# Main.net
KiCad netlist of a schematic drawn in Altium Designer
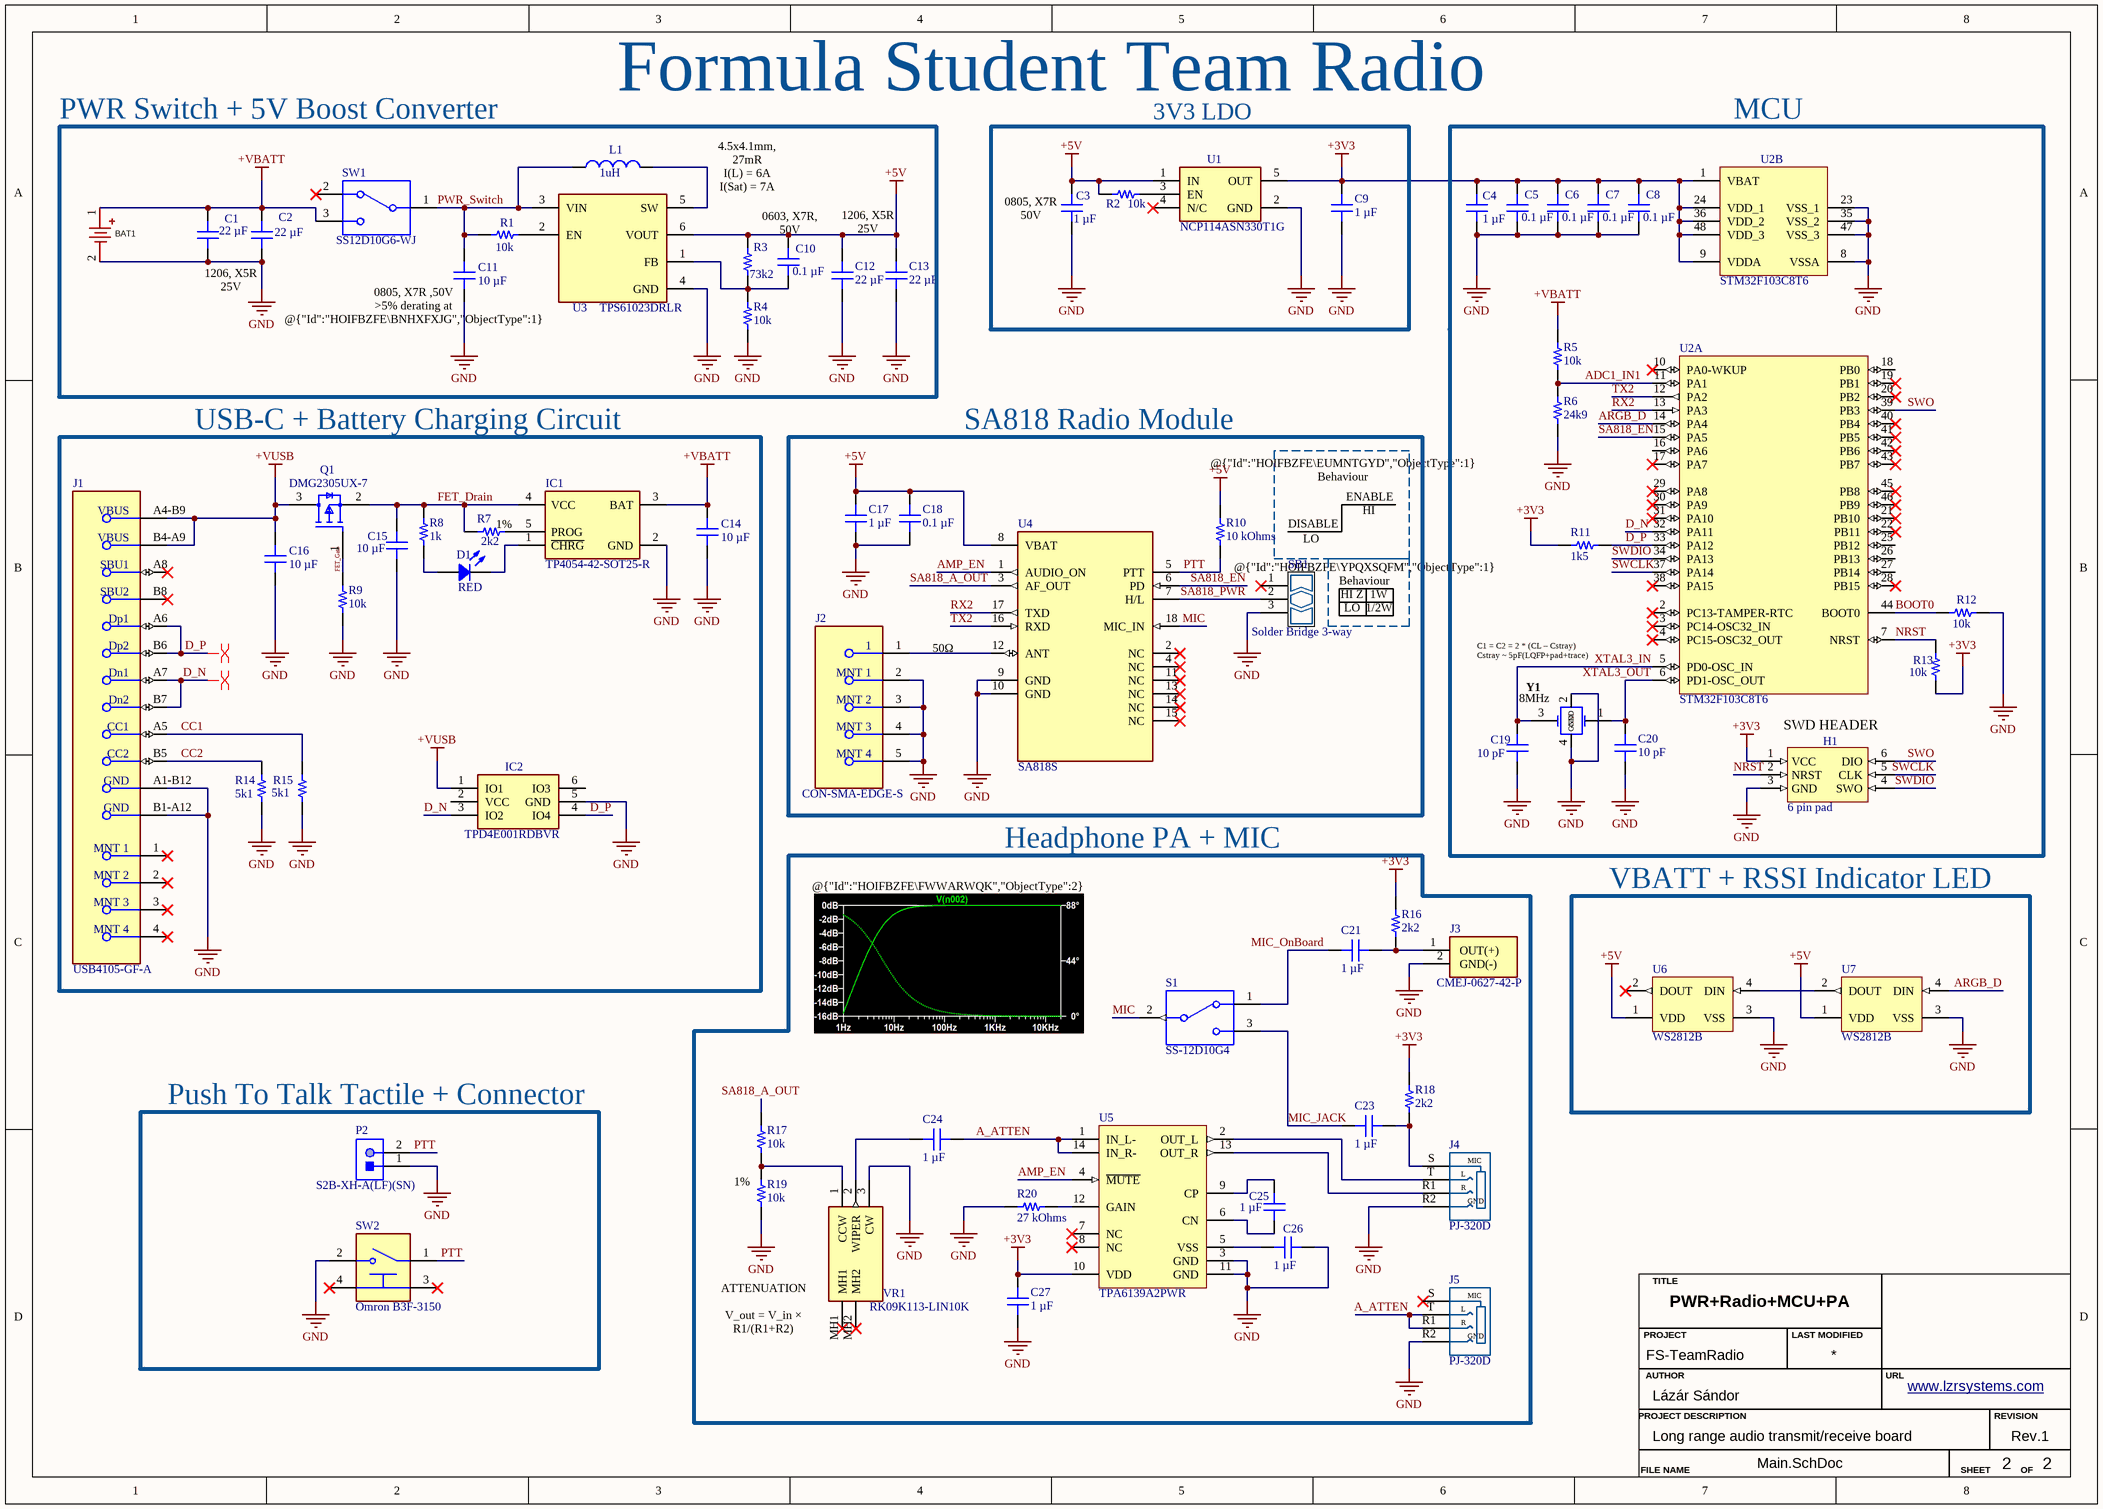
[diagram p0: Main.SchDoc]

(export (version "E")
  (design (tool "Eeschema 10.0.6"))
  (components
    (comp (ref "BAT1")
      (value "BH-123A-A1CJ002")
      (footprint "BAT-TH_BH-123A-A5BJ002")
      (fields (field (name "MANUFACTURER") "MYOUNG(美阳)"))
      (libsource (lib "Sandor Lazar") (part "BH-123A-A1CJ002"))
    )
    (comp (ref "C1")
      (value "22 µF")
      (footprint "MURATA CAP GRM31C 1206_3216")
      (description "CAP CER 22UF 25V X6S 1206")
      (fields
        (field (name "PART NUMBER") "GRM31CC81E226KE11L")
        (field (name "CAPACITANCE") "22 µF")
        (field (name "MANUFACTURER") "Murata Electronics")
      )
      (libsource (lib "Celestial Altium Library - altium_library") (part "Capacitor"))
    )
    (comp (ref "C2")
      (value "22 µF")
      (footprint "MURATA CAP GRM31C 1206_3216")
      (description "CAP CER 22UF 25V X6S 1206")
      (fields
        (field (name "PART NUMBER") "GRM31CC81E226KE11L")
        (field (name "CAPACITANCE") "22 µF")
        (field (name "MANUFACTURER") "Murata Electronics")
      )
      (libsource (lib "Celestial Altium Library - altium_library") (part "Capacitor"))
    )
    (comp (ref "C3")
      (value "1 µF")
      (footprint "MURATA GRT21 0805_2012")
      (description "CAP CER 1UF 50V X7R 0805")
      (fields
        (field (name "PART NUMBER") "GRT21BR71H105KE01L")
        (field (name "CAPACITANCE") "1 µF")
        (field (name "MANUFACTURER") "Murata Electronics")
      )
      (libsource (lib "Celestial Altium Library - altium_library") (part "Capacitor"))
    )
    (comp (ref "C4")
      (value "1 µF")
      (footprint "MURATA GRT21 0805_2012")
      (description "CAP CER 1UF 50V X7R 0805")
      (fields
        (field (name "PART NUMBER") "GRT21BR71H105KE01L")
        (field (name "CAPACITANCE") "1 µF")
        (field (name "MANUFACTURER") "Murata Electronics")
      )
      (libsource (lib "Celestial Altium Library - altium_library") (part "Capacitor"))
    )
    (comp (ref "C5")
      (value "0.1 µF")
      (footprint "CAP 0603_1608")
      (description "CAP CER 0.1UF 50V X7R 0603")
      (fields
        (field (name "PART NUMBER") "GCJ188R71H104KA12D")
        (field (name "CAPACITANCE") "0.1 µF")
        (field (name "MANUFACTURER") "Murata Electronics")
      )
      (libsource (lib "Celestial Altium Library - altium_library") (part "Capacitor"))
    )
    (comp (ref "C6")
      (value "0.1 µF")
      (footprint "CAP 0603_1608")
      (description "CAP CER 0.1UF 50V X7R 0603")
      (fields
        (field (name "PART NUMBER") "GCJ188R71H104KA12D")
        (field (name "CAPACITANCE") "0.1 µF")
        (field (name "MANUFACTURER") "Murata Electronics")
      )
      (libsource (lib "Celestial Altium Library - altium_library") (part "Capacitor"))
    )
    (comp (ref "C7")
      (value "0.1 µF")
      (footprint "CAP 0603_1608")
      (description "CAP CER 0.1UF 50V X7R 0603")
      (fields
        (field (name "PART NUMBER") "GCJ188R71H104KA12D")
        (field (name "CAPACITANCE") "0.1 µF")
        (field (name "MANUFACTURER") "Murata Electronics")
      )
      (libsource (lib "Celestial Altium Library - altium_library") (part "Capacitor"))
    )
    (comp (ref "C8")
      (value "0.1 µF")
      (footprint "CAP 0603_1608")
      (description "CAP CER 0.1UF 50V X7R 0603")
      (fields
        (field (name "PART NUMBER") "GCJ188R71H104KA12D")
        (field (name "CAPACITANCE") "0.1 µF")
        (field (name "MANUFACTURER") "Murata Electronics")
      )
      (libsource (lib "Celestial Altium Library - altium_library") (part "Capacitor"))
    )
    (comp (ref "C9")
      (value "1 µF")
      (footprint "MURATA GRT21 0805_2012")
      (description "CAP CER 1UF 50V X7R 0805")
      (fields
        (field (name "PART NUMBER") "GRT21BR71H105KE01L")
        (field (name "CAPACITANCE") "1 µF")
        (field (name "MANUFACTURER") "Murata Electronics")
      )
      (libsource (lib "Celestial Altium Library - altium_library") (part "Capacitor"))
    )
    (comp (ref "C10")
      (value "0.1 µF")
      (footprint "CAP 0603_1608")
      (description "CAP CER 0.1UF 50V X7R 0603")
      (fields
        (field (name "PART NUMBER") "GCJ188R71H104KA12D")
        (field (name "CAPACITANCE") "0.1 µF")
        (field (name "MANUFACTURER") "Murata Electronics")
      )
      (libsource (lib "Celestial Altium Library - altium_library") (part "Capacitor"))
    )
    (comp (ref "C11")
      (value "10 µF")
      (footprint "MURATA GRM21B 0805_2012")
      (description "CAP CER 10UF 50V X5R 0805")
      (fields
        (field (name "PART NUMBER") "GRM21BR61H106ME43L")
        (field (name "CAPACITANCE") "10 µF")
        (field (name "MANUFACTURER") "Murata Electronics")
      )
      (libsource (lib "Celestial Altium Library - altium_library") (part "Capacitor"))
    )
    (comp (ref "C12")
      (value "22 µF")
      (footprint "MURATA CAP GRM31C 1206_3216")
      (description "CAP CER 22UF 25V X6S 1206")
      (fields
        (field (name "PART NUMBER") "GRM31CC81E226KE11L")
        (field (name "CAPACITANCE") "22 µF")
        (field (name "MANUFACTURER") "Murata Electronics")
      )
      (libsource (lib "Celestial Altium Library - altium_library") (part "Capacitor"))
    )
    (comp (ref "C13")
      (value "22 µF")
      (footprint "MURATA CAP GRM31C 1206_3216")
      (description "CAP CER 22UF 25V X6S 1206")
      (fields
        (field (name "PART NUMBER") "GRM31CC81E226KE11L")
        (field (name "CAPACITANCE") "22 µF")
        (field (name "MANUFACTURER") "Murata Electronics")
      )
      (libsource (lib "Celestial Altium Library - altium_library") (part "Capacitor"))
    )
    (comp (ref "C14")
      (value "10 µF")
      (footprint "MURATA GRM21B 0805_2012")
      (description "CAP CER 10UF 50V X5R 0805")
      (fields
        (field (name "PART NUMBER") "GRM21BR61H106ME43L")
        (field (name "CAPACITANCE") "10 µF")
        (field (name "MANUFACTURER") "Murata Electronics")
      )
      (libsource (lib "Celestial Altium Library - altium_library") (part "Capacitor"))
    )
    (comp (ref "C15")
      (value "10 µF")
      (footprint "MURATA GRM21B 0805_2012")
      (description "CAP CER 10UF 50V X5R 0805")
      (fields
        (field (name "PART NUMBER") "GRM21BR61H106ME43L")
        (field (name "CAPACITANCE") "10 µF")
        (field (name "MANUFACTURER") "Murata Electronics")
      )
      (libsource (lib "Celestial Altium Library - altium_library") (part "Capacitor"))
    )
    (comp (ref "C16")
      (value "10 µF")
      (footprint "MURATA GRM21B 0805_2012")
      (description "CAP CER 10UF 50V X5R 0805")
      (fields
        (field (name "PART NUMBER") "GRM21BR61H106ME43L")
        (field (name "CAPACITANCE") "10 µF")
        (field (name "MANUFACTURER") "Murata Electronics")
      )
      (libsource (lib "Celestial Altium Library - altium_library") (part "Capacitor"))
    )
    (comp (ref "C17")
      (value "1 µF")
      (footprint "MURATA GRT21 0805_2012")
      (description "CAP CER 1UF 50V X7R 0805")
      (fields
        (field (name "PART NUMBER") "GRT21BR71H105KE01L")
        (field (name "CAPACITANCE") "1 µF")
        (field (name "MANUFACTURER") "Murata Electronics")
      )
      (libsource (lib "Celestial Altium Library - altium_library") (part "Capacitor"))
    )
    (comp (ref "C18")
      (value "0.1 µF")
      (footprint "CAP 0603_1608")
      (description "CAP CER 0.1UF 50V X7R 0603")
      (fields
        (field (name "PART NUMBER") "GCJ188R71H104KA12D")
        (field (name "CAPACITANCE") "0.1 µF")
        (field (name "MANUFACTURER") "Murata Electronics")
      )
      (libsource (lib "Celestial Altium Library - altium_library") (part "Capacitor"))
    )
    (comp (ref "C19")
      (value "10 pF")
      (footprint "MURATA GCM188 0603_1608")
      (description "CAP CER 10PF 100V C0G/NP0 0603")
      (fields
        (field (name "PART NUMBER") "GCM1885C2A100FA16D")
        (field (name "CAPACITANCE") "10 pF")
        (field (name "MANUFACTURER") "Murata Electronics")
      )
      (libsource (lib "Celestial Altium Library - altium_library") (part "Capacitor"))
    )
    (comp (ref "C20")
      (value "10 pF")
      (footprint "MURATA GCM188 0603_1608")
      (description "CAP CER 10PF 100V C0G/NP0 0603")
      (fields
        (field (name "PART NUMBER") "GCM1885C2A100FA16D")
        (field (name "CAPACITANCE") "10 pF")
        (field (name "MANUFACTURER") "Murata Electronics")
      )
      (libsource (lib "Celestial Altium Library - altium_library") (part "Capacitor"))
    )
    (comp (ref "C21")
      (value "1 µF")
      (footprint "MURATA GRT21 0805_2012")
      (description "CAP CER 1UF 50V X7R 0805")
      (fields
        (field (name "PART NUMBER") "GRT21BR71H105KE01L")
        (field (name "CAPACITANCE") "1 µF")
        (field (name "MANUFACTURER") "Murata Electronics")
      )
      (libsource (lib "Celestial Altium Library - altium_library") (part "Capacitor"))
    )
    (comp (ref "C23")
      (value "1 µF")
      (footprint "MURATA GRT21 0805_2012")
      (description "CAP CER 1UF 50V X7R 0805")
      (fields
        (field (name "PART NUMBER") "GRT21BR71H105KE01L")
        (field (name "CAPACITANCE") "1 µF")
        (field (name "MANUFACTURER") "Murata Electronics")
      )
      (libsource (lib "Celestial Altium Library - altium_library") (part "Capacitor"))
    )
    (comp (ref "C24")
      (value "1 µF")
      (footprint "MURATA GRT21 0805_2012")
      (description "CAP CER 1UF 50V X7R 0805")
      (fields
        (field (name "PART NUMBER") "GRT21BR71H105KE01L")
        (field (name "CAPACITANCE") "1 µF")
        (field (name "MANUFACTURER") "Murata Electronics")
      )
      (libsource (lib "Celestial Altium Library - altium_library") (part "Capacitor"))
    )
    (comp (ref "C25")
      (value "1 µF")
      (footprint "MURATA GRT21 0805_2012")
      (description "CAP CER 1UF 50V X7R 0805")
      (fields
        (field (name "PART NUMBER") "GRT21BR71H105KE01L")
        (field (name "CAPACITANCE") "1 µF")
        (field (name "MANUFACTURER") "Murata Electronics")
      )
      (libsource (lib "Celestial Altium Library - altium_library") (part "Capacitor"))
    )
    (comp (ref "C26")
      (value "1 µF")
      (footprint "MURATA GRT21 0805_2012")
      (description "CAP CER 1UF 50V X7R 0805")
      (fields
        (field (name "PART NUMBER") "GRT21BR71H105KE01L")
        (field (name "CAPACITANCE") "1 µF")
        (field (name "MANUFACTURER") "Murata Electronics")
      )
      (libsource (lib "Celestial Altium Library - altium_library") (part "Capacitor"))
    )
    (comp (ref "C27")
      (value "1 µF")
      (footprint "MURATA GRT21 0805_2012")
      (description "CAP CER 1UF 50V X7R 0805")
      (fields
        (field (name "PART NUMBER") "GRT21BR71H105KE01L")
        (field (name "CAPACITANCE") "1 µF")
        (field (name "MANUFACTURER") "Murata Electronics")
      )
      (libsource (lib "Celestial Altium Library - altium_library") (part "Capacitor"))
    )
    (comp (ref "D1")
      (value "RED")
      (footprint "LED 0603_1608 RED")
      (description "LED RED DIFFUSED 0603 SMD")
      (fields
        (field (name "PART NUMBER") "B1931URO-20D000114U1930")
        (field (name "MANUFACTURER") "Harvatek Corporation")
      )
      (libsource (lib "Celestial Altium Library - altium_library") (part "LED"))
    )
    (comp (ref "H1")
      (value "6 pin pad")
      (footprint "6 pin pad-Footprint-1")
      (libsource (lib "Sandor Lazar") (part "SWD-1.27mm-2x03"))
    )
    (comp (ref "IC1")
      (value "TP4054-42-SOT25-R")
      (footprint "SamacSys:SOT95P280X100-5N")
      (description "Integrated Circuit")
      (libsource (lib "SamacSys") (part "TP4054-42-SOT25-R"))
    )
    (comp (ref "IC2")
      (value "TPD4E001RDBVR")
      (footprint "SamacSys:SOT95P280X145-6N")
      (description "Integrated Circuit")
      (fields (field (name "MOUSER PART NUMBER") "595-TPD4E001RDBVR"))
      (libsource (lib "*") (part "TPD4E001RDBVR"))
    )
    (comp (ref "J1")
      (value "USB4105-GF-A")
      (footprint "FP-USB4105-GF-A-MFG")
      (description "Conn USB 2.0 Type C RCP 24 POS 0.3mm/0.5mm Solder RA SMD 24 Terminal 1 Port T/R")
      (libsource (lib "Sandor Lazar") (part "e7c17a616881a82b79941196b4bec10"))
    )
    (comp (ref "J2")
      (value "CON-SMA-EDGE-S")
      (footprint "FP-CON-SMA-EDGE-S-MFG")
      (description "Sma Female Connector, Pcb Edge Mount Rohs Compliant: Yes")
      (libsource (lib "Sandor Lazar") (part "a163d97a771fcdd2fd1f1a9264c171f"))
    )
    (comp (ref "J3")
      (value "CMEJ-0627-42-P")
      (footprint "SamacSys:CMEJ062742P")
      (description "Connector")
      (fields (field (name "MOUSER PART NUMBER") "490-CMEJ-0627-42-P"))
      (libsource (lib "SamacSys") (part "CMEJ-0627-42-P"))
    )
    (comp (ref "J4")
      (value "PJ-320D")
      (footprint "SamacSys:PJ320D")
      (description "Connector")
      (libsource (lib "SamacSys") (part "PJ-320D"))
    )
    (comp (ref "J5")
      (value "PJ-320D")
      (footprint "SamacSys:PJ320D")
      (description "Connector")
      (libsource (lib "SamacSys") (part "PJ-320D"))
    )
    (comp (ref "L1")
      (value "1uH")
      (footprint "INDM4843X20N")
      (description "1uH, 6A, 27mR, SMD 4.5x4.1mm")
      (libsource (lib "Sandor Lazar") (part "IND-2"))
    )
    (comp (ref "P2")
      (value "S2B-XH-A(LF)(SN)")
      (footprint "JST-S2B-XH-A(LF)(SN)_V")
      (fields (field (name "MANUFACTURER") "JST"))
      (libsource (lib "Sandor Lazar") (part "CN-1P-M-R2"))
    )
    (comp (ref "Q1")
      (value "DMG2305UX-7")
      (footprint "FP-SOT23-IPC_C")
      (description "P-Channel 20 V 52 mOhm Surface Mount Enhancement Mode Mosfet - SOT-23-3")
      (libsource (lib "Sandor Lazar") (part "87831b450059b469d4a68f5364f4496"))
    )
    (comp (ref "R1")
      (value "10k")
      (footprint "RES 0603_1608")
      (description "RES SMD 10K OHM 5% 1/4W 0603")
      (fields (field (name "PART NUMBER") "RCS060310K0JNEA") (field (name "MANUFACTURER") "Vishay Dale"))
      (libsource (lib "Celestial Altium Library - altium_library") (part "Resistor"))
    )
    (comp (ref "R2")
      (value "10k")
      (footprint "RES 0603_1608")
      (description "RES SMD 10K OHM 5% 1/4W 0603")
      (fields (field (name "PART NUMBER") "RCS060310K0JNEA") (field (name "MANUFACTURER") "Vishay Dale"))
      (libsource (lib "Celestial Altium Library - altium_library") (part "Resistor"))
    )
    (comp (ref "R3")
      (value "73k2")
      (footprint "RES 0603_1608")
      (description "ANTI-SURGE CHIP RESISTORS")
      (fields (field (name "PART NUMBER") "ESR03EZPF7322") (field (name "MANUFACTURER") "Rohm Semiconductor"))
      (libsource (lib "Celestial Altium Library - altium_library") (part "Resistor"))
    )
    (comp (ref "R4")
      (value "10k")
      (footprint "RES 0603_1608")
      (description "RES 10K OHM 0.1% 1/10W 0603")
      (fields (field (name "PART NUMBER") "TNPW060310K0BETA") (field (name "MANUFACTURER") "Vishay Dale"))
      (libsource (lib "Celestial Altium Library - altium_library") (part "Resistor"))
    )
    (comp (ref "R5")
      (value "10k")
      (footprint "RES 0603_1608")
      (description "RES 10K OHM 0.1% 1/10W 0603")
      (fields (field (name "PART NUMBER") "TNPW060310K0BETA") (field (name "MANUFACTURER") "Vishay Dale"))
      (libsource (lib "Celestial Altium Library - altium_library") (part "Resistor"))
    )
    (comp (ref "R6")
      (value "24k9")
      (footprint "RES 0603_1608")
      (description "RQ 0603 24K9 0.1% 10PPM 1K RL")
      (fields
        (field (name "PART NUMBER") "RQ73C1J24K9BTDF")
        (field (name "MANUFACTURER") "TE Connectivity Passive Product")
      )
      (libsource (lib "Celestial Altium Library - altium_library") (part "Resistor"))
    )
    (comp (ref "R7")
      (value "2k2")
      (footprint "RES 0603_1608")
      (description "RES CHIP 0603 2K2 1% 1/4W TC100")
      (fields (field (name "PART NUMBER") "CMP0603QFX-2201ELF") (field (name "MANUFACTURER") "Bourns Inc."))
      (libsource (lib "Celestial Altium Library - altium_library") (part "Resistor"))
    )
    (comp (ref "R8")
      (value "1k")
      (footprint "RES 0603_1608")
      (description "RES 10K OHM 0.1% 1/10W 0603")
      (fields (field (name "PART NUMBER") "TNPW060310K0BETA") (field (name "MANUFACTURER") "Vishay Dale"))
      (libsource (lib "Celestial Altium Library - altium_library") (part "Resistor"))
    )
    (comp (ref "R9")
      (value "10k")
      (footprint "RES 0603_1608")
      (description "RES 10K OHM 0.1% 1/10W 0603")
      (fields (field (name "PART NUMBER") "TNPW060310K0BETA") (field (name "MANUFACTURER") "Vishay Dale"))
      (libsource (lib "Celestial Altium Library - altium_library") (part "Resistor"))
    )
    (comp (ref "R10")
      (value "10 kOhms")
      (footprint "RES 0603_1608")
      (description "RES SMD 10K OHM 5% 1/4W 0603")
      (fields (field (name "PART NUMBER") "RCS060310K0JNEA") (field (name "MANUFACTURER") "Vishay Dale"))
      (libsource (lib "Celestial Altium Library - altium_library") (part "Resistor"))
    )
    (comp (ref "R11")
      (value "1k5")
      (footprint "RES 0603_1608")
      (description "RES 1.5K OHM 1% 1/8W 0603")
      (fields
        (field (name "PART NUMBER") "RNCP0603FTD1K50")
        (field (name "MANUFACTURER") "Stackpole Electronics Inc")
      )
      (libsource (lib "Celestial Altium Library - altium_library") (part "Resistor"))
    )
    (comp (ref "R12")
      (value "10k")
      (footprint "RES 0603_1608")
      (description "RES 10K OHM 5% 1/10W 0603")
      (fields (field (name "PART NUMBER") "CRCW060310K0JNEAC") (field (name "MANUFACTURER") "Vishay Dale"))
      (libsource (lib "Celestial Altium Library - altium_library") (part "Resistor"))
    )
    (comp (ref "R13")
      (value "10k")
      (footprint "RES 0603_1608")
      (description "RES 10K OHM 5% 1/10W 0603")
      (fields (field (name "PART NUMBER") "CRCW060310K0JNEAC") (field (name "MANUFACTURER") "Vishay Dale"))
      (libsource (lib "Celestial Altium Library - altium_library") (part "Resistor"))
    )
    (comp (ref "R14")
      (value "5k1")
      (footprint "KOA RES RK73 RN73 0603_1608")
      (description "RESISTOR")
      (fields
        (field (name "PART NUMBER") "RK73B1JTTDD512J")
        (field (name "MANUFACTURER") "KOA Speer Electronics, Inc.")
      )
      (libsource (lib "Celestial Altium Library - altium_library") (part "Resistor"))
    )
    (comp (ref "R15")
      (value "5k1")
      (footprint "KOA RES RK73 RN73 0603_1608")
      (description "RESISTOR")
      (fields
        (field (name "PART NUMBER") "RK73B1JTTDD512J")
        (field (name "MANUFACTURER") "KOA Speer Electronics, Inc.")
      )
      (libsource (lib "Celestial Altium Library - altium_library") (part "Resistor"))
    )
    (comp (ref "R16")
      (value "2k2")
      (footprint "RES 0603_1608")
      (description "RES CHIP 0603 2K2 1% 1/4W TC100")
      (fields (field (name "PART NUMBER") "CMP0603QFX-2201ELF") (field (name "MANUFACTURER") "Bourns Inc."))
      (libsource (lib "Celestial Altium Library - altium_library") (part "Resistor"))
    )
    (comp (ref "R17")
      (value "10k")
      (footprint "RES 0603_1608")
      (description "RES 10K OHM 0.1% 1/10W 0603")
      (fields (field (name "PART NUMBER") "TNPW060310K0BETA") (field (name "MANUFACTURER") "Vishay Dale"))
      (libsource (lib "Celestial Altium Library - altium_library") (part "Resistor"))
    )
    (comp (ref "R18")
      (value "2k2")
      (footprint "RES 0603_1608")
      (description "RES CHIP 0603 2K2 1% 1/4W TC100")
      (fields (field (name "PART NUMBER") "CMP0603QFX-2201ELF") (field (name "MANUFACTURER") "Bourns Inc."))
      (libsource (lib "Celestial Altium Library - altium_library") (part "Resistor"))
    )
    (comp (ref "R19")
      (value "10k")
      (footprint "RES 0603_1608")
      (description "RES CHIP 0603 2K2 1% 1/4W TC100")
      (fields (field (name "PART NUMBER") "CMP0603QFX-2201ELF") (field (name "MANUFACTURER") "Bourns Inc."))
      (libsource (lib "Celestial Altium Library - altium_library") (part "Resistor"))
    )
    (comp (ref "R20")
      (value "27 kOhms")
      (footprint "RES 0603_1608")
      (description "RES 27K OHM 5% 1/10W 0603")
      (fields (field (name "PART NUMBER") "CRCW060327K0JNEAC") (field (name "MANUFACTURER") "Vishay Dale"))
      (libsource (lib "Celestial Altium Library - altium_library") (part "Resistor"))
    )
    (comp (ref "S1")
      (value "SS-12D10G4")
      (footprint "SamacSys:SS12D10G4")
      (description "Switch")
      (libsource (lib "SamacSys") (part "SS-12D10G4"))
    )
    (comp (ref "SB1")
      (value "Solder Bridge 3-way")
      (footprint "Solder Bridge 3-way-Footprint-1")
      (description "3-way solder bridge mainly for power rail selection")
      (libsource (lib "Sandor Lazar") (part "Solder Bridge 3-way"))
    )
    (comp (ref "SW1")
      (value "SS12D10G6-WJ")
      (footprint "SHOU HAN SS12D10G6-WJ-Footprint-1")
      (description "TH Right angle SPDT 3A Slide switch")
      (libsource (lib "Sandor Lazar") (part "SS12D10G"))
    )
    (comp (ref "SW2")
      (value "Omron B3F-3150")
      (footprint "FP-B3F-3150-MFG")
      (description "Switch Tactile N.O. SPST Projected Plunger PC Pins 0.05A 24VDC 1000000Cycle 0.98N Thru-Hole Bag")
      (libsource (lib "Sandor Lazar") (part "233cb25b8eba039064bc1ca6c1965ae"))
    )
    (comp (ref "U1")
      (value "NCP114ASN330T1G")
      (footprint "SamacSys:SOT95P275X110-5N")
      (description "Power Supply")
      (fields (field (name "MOUSER PART NUMBER") "863-NCP114ASN330T1G"))
      (libsource (lib "SamacSys") (part "NCP114ASN330T1G"))
    )
    (comp (ref "U2")
      (value "STM32F103C8T6")
      (footprint "STM-LQFP48_L")
      (description "RISC Microcontroller, 32-Bit, FLASH, STM32 CPU, 72MHz, CMOS, PQFP48")
      (libsource (lib "") (part "MC-ARM-STM32F103X8_B-SQ48_1"))
    )
    (comp (ref "U3")
      (value "TPS61023DRLR")
      (footprint "FP-DRL0006A-MFG")
      (description "Switching Voltage Regulators 3.7-A boost converter with 0.5-V ultra-low input vo")
      (libsource (lib "Sandor Lazar") (part "b28b3e956a4ad07201ce69f9d09f9a8"))
    )
    (comp (ref "U4")
      (value "SA818S")
      (footprint "XCVR_SA818S")
      (description "Walkie talkie module with RDA1846S chip")
      (fields (field (name "MF") "G-nicerf"))
      (libsource (lib "Sandor Lazar") (part "SA818S"))
    )
    (comp (ref "U5")
      (value "TPA6139A2PWR")
      (footprint "PW0014A_N")
      (description "25-mW, stereo, analog input headphone amplifier with programmable gain 14-TSSOP -40 to 85")
      (libsource (lib "Sandor Lazar") (part "TI-TPA6139A2PW14"))
    )
    (comp (ref "U6")
      (value "WS2812B")
      (footprint "ADAI-WS2812B_V")
      (fields (field (name "MANUFACTURER") "Adafruit Industries"))
      (libsource (lib "Sandor Lazar") (part "ADAI-WS2812B-4"))
    )
    (comp (ref "U7")
      (value "WS2812B")
      (footprint "ADAI-WS2812B_V")
      (fields (field (name "MANUFACTURER") "Adafruit Industries"))
      (libsource (lib "Sandor Lazar") (part "ADAI-WS2812B-4"))
    )
    (comp (ref "VR1")
      (value "RK09K113-LIN10K")
      (footprint "SamacSys:RK09K113LIN10K")
      (description "Variable Resistor")
      (libsource (lib "*") (part "RK09K113-LIN10K"))
    )
    (comp (ref "Y1")
      (value "8MHz")
      (footprint "Yajingxin TX32258M4DBDD2T-Footprint-1")
      (description "8 MHz crystal, CL: 10pF, +/-10ppm")
      (libsource (lib "Sandor Lazar") (part "XTAL-2"))
    )
  )
  (nets
    (net (code "1") (name "+3V3") (class "Default")
      (node (ref "C27") (pin "1") (pinfunction "1_1") (pintype "passive"))
      (node (ref "C4") (pin "2") (pinfunction "2_2") (pintype "passive"))
      (node (ref "C5") (pin "2") (pinfunction "2_2") (pintype "passive"))
      (node (ref "C6") (pin "2") (pinfunction "2_2") (pintype "passive"))
      (node (ref "C7") (pin "2") (pinfunction "2_2") (pintype "passive"))
      (node (ref "C8") (pin "2") (pinfunction "2_2") (pintype "passive"))
      (node (ref "C9") (pin "2") (pinfunction "2_2") (pintype "passive"))
      (node (ref "H1") (pin "1") (pinfunction "VCC_1") (pintype "input"))
      (node (ref "R11") (pin "2") (pinfunction "2_2") (pintype "passive"))
      (node (ref "R13") (pin "2") (pinfunction "2_2") (pintype "passive"))
      (node (ref "R16") (pin "2") (pinfunction "2_2") (pintype "passive"))
      (node (ref "R18") (pin "1") (pinfunction "1_1") (pintype "passive"))
      (node (ref "U1") (pin "5") (pinfunction "OUT_5") (pintype "power_in"))
      (node (ref "U2") (pin "1") (pinfunction "VBAT_1") (pintype "power_in"))
      (node (ref "U2") (pin "24") (pinfunction "VDD_1_24") (pintype "power_in"))
      (node (ref "U2") (pin "36") (pinfunction "VDD_2_36") (pintype "power_in"))
      (node (ref "U2") (pin "48") (pinfunction "VDD_3_48") (pintype "power_in"))
      (node (ref "U2") (pin "9") (pinfunction "VDDA_9") (pintype "power_in"))
      (node (ref "U5") (pin "10") (pinfunction "VDD_10") (pintype "power_in"))
    )
    (net (code "2") (name "+5V") (class "Default")
      (node (ref "C10") (pin "2") (pinfunction "2_2") (pintype "passive"))
      (node (ref "C12") (pin "2") (pinfunction "2_2") (pintype "passive"))
      (node (ref "C13") (pin "2") (pinfunction "2_2") (pintype "passive"))
      (node (ref "C17") (pin "2") (pinfunction "2_2") (pintype "passive"))
      (node (ref "C18") (pin "2") (pinfunction "2_2") (pintype "passive"))
      (node (ref "C3") (pin "2") (pinfunction "2_2") (pintype "passive"))
      (node (ref "R10") (pin "2") (pinfunction "2_2") (pintype "passive"))
      (node (ref "R2") (pin "1") (pinfunction "1_1") (pintype "passive"))
      (node (ref "R3") (pin "2") (pinfunction "2_2") (pintype "passive"))
      (node (ref "U1") (pin "1") (pinfunction "IN_1") (pintype "power_in"))
      (node (ref "U3") (pin "6") (pinfunction "VOUT_6") (pintype "power_in"))
      (node (ref "U4") (pin "8") (pinfunction "VBAT_8") (pintype "power_in"))
      (node (ref "U6") (pin "1") (pinfunction "VDD_1") (pintype "power_in"))
      (node (ref "U7") (pin "1") (pinfunction "VDD_1") (pintype "power_in"))
    )
    (net (code "3") (name "+VBATT") (class "Default")
      (node (ref "BAT1") (pin "1") (pinfunction "1_1") (pintype "passive"))
      (node (ref "C1") (pin "2") (pinfunction "2_2") (pintype "passive"))
      (node (ref "C14") (pin "2") (pinfunction "2_2") (pintype "passive"))
      (node (ref "C2") (pin "2") (pinfunction "2_2") (pintype "passive"))
      (node (ref "IC1") (pin "3") (pinfunction "BAT_3") (pintype "passive"))
      (node (ref "R5") (pin "2") (pinfunction "2_2") (pintype "passive"))
      (node (ref "SW1") (pin "3") (pinfunction "1_3") (pintype "passive"))
    )
    (net (code "4") (name "+VUSB") (class "Default")
      (node (ref "C16") (pin "2") (pinfunction "2_2") (pintype "passive"))
      (node (ref "IC2") (pin "1") (pinfunction "IO1_1") (pintype "passive"))
      (node (ref "J1") (pin "A4-B9") (pinfunction "VBUS_A4-B9") (pintype "power_in"))
      (node (ref "J1") (pin "B4-A9") (pinfunction "VBUS_B4-A9") (pintype "power_in"))
      (node (ref "Q1") (pin "3") (pinfunction "DRAIN_3") (pintype "passive"))
    )
    (net (code "5") (name "/ADC1_IN1") (class "Default")
      (node (ref "R5") (pin "1") (pinfunction "1_1") (pintype "passive"))
      (node (ref "R6") (pin "2") (pinfunction "2_2") (pintype "passive"))
      (node (ref "U2") (pin "11") (pinfunction "PA1_11") (pintype "bidirectional"))
    )
    (net (code "6") (name "/AMP_EN") (class "Default")
      (node (ref "U4") (pin "1") (pinfunction "AUDIO_ON_1") (pintype "output"))
      (node (ref "U5") (pin "4") (pinfunction "~{MUTE}_4") (pintype "input"))
    )
    (net (code "7") (name "/ARGB_D") (class "Default")
      (node (ref "U2") (pin "14") (pinfunction "PA4_14") (pintype "bidirectional"))
      (node (ref "U7") (pin "4") (pinfunction "DIN_4") (pintype "input"))
    )
    (net (code "8") (name "/A_ATTEN") (class "Default")
      (node (ref "C24") (pin "1") (pinfunction "1_1") (pintype "passive"))
      (node (ref "J5") (pin "R1") (pinfunction "3_R1") (pintype "passive"))
      (node (ref "J5") (pin "T") (pinfunction "2_T") (pintype "passive"))
      (node (ref "U5") (pin "1") (pinfunction "IN_L-_1") (pintype "power_in"))
      (node (ref "U5") (pin "14") (pinfunction "IN_R-_14") (pintype "power_in"))
    )
    (net (code "9") (name "/BOOT0") (class "Default")
      (node (ref "R12") (pin "2") (pinfunction "2_2") (pintype "passive"))
      (node (ref "U2") (pin "44") (pinfunction "BOOT0_44") (pintype "passive"))
    )
    (net (code "10") (name "/CC1") (class "Default")
      (node (ref "J1") (pin "A5") (pinfunction "CC1_A5") (pintype "bidirectional"))
      (node (ref "R15") (pin "2") (pinfunction "2_2") (pintype "passive"))
    )
    (net (code "11") (name "/CC2") (class "Default")
      (node (ref "J1") (pin "B5") (pinfunction "CC2_B5") (pintype "bidirectional"))
      (node (ref "R14") (pin "2") (pinfunction "2_2") (pintype "passive"))
    )
    (net (code "12") (name "/D_N") (class "Default")
      (node (ref "IC2") (pin "3") (pinfunction "IO2_3") (pintype "passive"))
      (node (ref "J1") (pin "A7") (pinfunction "Dn1_A7") (pintype "bidirectional"))
      (node (ref "J1") (pin "B7") (pinfunction "Dn2_B7") (pintype "bidirectional"))
      (node (ref "U2") (pin "32") (pinfunction "PA11_32") (pintype "bidirectional"))
    )
    (net (code "13") (name "/D_P") (class "Default")
      (node (ref "IC2") (pin "4") (pinfunction "IO4_4") (pintype "passive"))
      (node (ref "J1") (pin "A6") (pinfunction "Dp1_A6") (pintype "bidirectional"))
      (node (ref "J1") (pin "B6") (pinfunction "Dp2_B6") (pintype "bidirectional"))
      (node (ref "R11") (pin "1") (pinfunction "1_1") (pintype "passive"))
      (node (ref "U2") (pin "33") (pinfunction "PA12_33") (pintype "bidirectional"))
    )
    (net (code "14") (name "/FET_Drain") (class "Default")
      (node (ref "C15") (pin "2") (pinfunction "2_2") (pintype "passive"))
      (node (ref "IC1") (pin "4") (pinfunction "VCC_4") (pintype "passive"))
      (node (ref "Q1") (pin "2") (pinfunction "SOURCE_2") (pintype "passive"))
      (node (ref "R7") (pin "1") (pinfunction "1_1") (pintype "passive"))
      (node (ref "R8") (pin "2") (pinfunction "2_2") (pintype "passive"))
    )
    (net (code "15") (name "/FET_Gate") (class "Default")
      (node (ref "Q1") (pin "1") (pinfunction "GATE_1") (pintype "passive"))
      (node (ref "R9") (pin "2") (pinfunction "2_2") (pintype "passive"))
    )
    (net (code "16") (name "/MIC") (class "Default")
      (node (ref "S1") (pin "2") (pinfunction "1_2") (pintype "output"))
      (node (ref "U4") (pin "18") (pinfunction "MIC_IN_18") (pintype "input"))
    )
    (net (code "17") (name "/MIC_JACK") (class "Default")
      (node (ref "C23") (pin "2") (pinfunction "2_2") (pintype "passive"))
      (node (ref "S1") (pin "3") (pinfunction "1_3") (pintype "passive"))
    )
    (net (code "18") (name "/MIC_OnBoard") (class "Default")
      (node (ref "C21") (pin "2") (pinfunction "2_2") (pintype "passive"))
      (node (ref "S1") (pin "1") (pinfunction "1_1") (pintype "passive"))
    )
    (net (code "19") (name "/NRST") (class "Default")
      (node (ref "H1") (pin "2") (pinfunction "NRST_2") (pintype "input"))
      (node (ref "R13") (pin "1") (pinfunction "1_1") (pintype "passive"))
      (node (ref "U2") (pin "7") (pinfunction "NRST_7") (pintype "bidirectional"))
    )
    (net (code "20") (name "/PTT") (class "Default")
      (node (ref "P2") (pin "2") (pinfunction "2_2") (pintype "passive"))
      (node (ref "R10") (pin "1") (pinfunction "1_1") (pintype "passive"))
      (node (ref "SW2") (pin "1") (pinfunction "1_1") (pintype "passive"))
      (node (ref "U4") (pin "5") (pinfunction "PTT_5") (pintype "passive"))
    )
    (net (code "21") (name "/PWR_Switch") (class "Default")
      (node (ref "C11") (pin "2") (pinfunction "2_2") (pintype "passive"))
      (node (ref "L1") (pin "1") (pinfunction "1_1") (pintype "passive"))
      (node (ref "R1") (pin "1") (pinfunction "1_1") (pintype "passive"))
      (node (ref "SW1") (pin "1") (pinfunction "1_1") (pintype "passive"))
      (node (ref "U3") (pin "3") (pinfunction "VIN_3") (pintype "power_in"))
    )
    (net (code "22") (name "/RX2") (class "Default")
      (node (ref "U2") (pin "13") (pinfunction "PA3_13") (pintype "input"))
      (node (ref "U4") (pin "17") (pinfunction "TXD_17") (pintype "output"))
    )
    (net (code "23") (name "/SA818_A_OUT") (class "Default")
      (node (ref "R17") (pin "2") (pinfunction "2_2") (pintype "passive"))
      (node (ref "U4") (pin "3") (pinfunction "AF_OUT_3") (pintype "output"))
    )
    (net (code "24") (name "/SA818_EN") (class "Default")
      (node (ref "U2") (pin "15") (pinfunction "PA5_15") (pintype "bidirectional"))
      (node (ref "U4") (pin "6") (pinfunction "PD_6") (pintype "input"))
    )
    (net (code "25") (name "/SA818_PWR") (class "Default")
      (node (ref "SB1") (pin "2") (pinfunction "2_2") (pintype "passive"))
      (node (ref "U4") (pin "7") (pinfunction "H/L_7") (pintype "passive"))
    )
    (net (code "26") (name "/SWCLK") (class "Default")
      (node (ref "H1") (pin "5") (pinfunction "CLK_5") (pintype "input"))
      (node (ref "U2") (pin "37") (pinfunction "PA14_37") (pintype "bidirectional"))
    )
    (net (code "27") (name "/SWDIO") (class "Default")
      (node (ref "H1") (pin "4") (pinfunction "SWO_4") (pintype "input"))
      (node (ref "U2") (pin "34") (pinfunction "PA13_34") (pintype "bidirectional"))
    )
    (net (code "28") (name "/SWO") (class "Default")
      (node (ref "H1") (pin "6") (pinfunction "DIO_6") (pintype "input"))
      (node (ref "U2") (pin "39") (pinfunction "PB3_39") (pintype "bidirectional"))
    )
    (net (code "29") (name "/TX2") (class "Default")
      (node (ref "U2") (pin "12") (pinfunction "PA2_12") (pintype "output"))
      (node (ref "U4") (pin "16") (pinfunction "RXD_16") (pintype "input"))
    )
    (net (code "30") (name "/XTAL3_IN") (class "Default")
      (node (ref "C19") (pin "2") (pinfunction "2_2") (pintype "passive"))
      (node (ref "U2") (pin "5") (pinfunction "PD0-OSC_IN_5") (pintype "bidirectional"))
      (node (ref "Y1") (pin "3") (pinfunction "3_3") (pintype "passive"))
    )
    (net (code "31") (name "/XTAL3_OUT") (class "Default")
      (node (ref "C20") (pin "2") (pinfunction "2_2") (pintype "passive"))
      (node (ref "U2") (pin "6") (pinfunction "PD1-OSC_OUT_6") (pintype "bidirectional"))
      (node (ref "Y1") (pin "1") (pinfunction "1_1") (pintype "passive"))
    )
    (net (code "32") (name "GND") (class "Default")
      (node (ref "BAT1") (pin "2") (pinfunction "2_2") (pintype "passive"))
      (node (ref "C1") (pin "1") (pinfunction "1_1") (pintype "passive"))
      (node (ref "C11") (pin "1") (pinfunction "1_1") (pintype "passive"))
      (node (ref "C12") (pin "1") (pinfunction "1_1") (pintype "passive"))
      (node (ref "C13") (pin "1") (pinfunction "1_1") (pintype "passive"))
      (node (ref "C14") (pin "1") (pinfunction "1_1") (pintype "passive"))
      (node (ref "C15") (pin "1") (pinfunction "1_1") (pintype "passive"))
      (node (ref "C16") (pin "1") (pinfunction "1_1") (pintype "passive"))
      (node (ref "C17") (pin "1") (pinfunction "1_1") (pintype "passive"))
      (node (ref "C18") (pin "1") (pinfunction "1_1") (pintype "passive"))
      (node (ref "C19") (pin "1") (pinfunction "1_1") (pintype "passive"))
      (node (ref "C2") (pin "1") (pinfunction "1_1") (pintype "passive"))
      (node (ref "C20") (pin "1") (pinfunction "1_1") (pintype "passive"))
      (node (ref "C26") (pin "2") (pinfunction "2_2") (pintype "passive"))
      (node (ref "C27") (pin "2") (pinfunction "2_2") (pintype "passive"))
      (node (ref "C3") (pin "1") (pinfunction "1_1") (pintype "passive"))
      (node (ref "C4") (pin "1") (pinfunction "1_1") (pintype "passive"))
      (node (ref "C5") (pin "1") (pinfunction "1_1") (pintype "passive"))
      (node (ref "C6") (pin "1") (pinfunction "1_1") (pintype "passive"))
      (node (ref "C7") (pin "1") (pinfunction "1_1") (pintype "passive"))
      (node (ref "C8") (pin "1") (pinfunction "1_1") (pintype "passive"))
      (node (ref "C9") (pin "1") (pinfunction "1_1") (pintype "passive"))
      (node (ref "H1") (pin "3") (pinfunction "GND_3") (pintype "input"))
      (node (ref "IC1") (pin "2") (pinfunction "GND_2") (pintype "passive"))
      (node (ref "IC2") (pin "5") (pinfunction "GND_5") (pintype "passive"))
      (node (ref "J1") (pin "A1-B12") (pinfunction "GND_A1-B12") (pintype "power_in"))
      (node (ref "J1") (pin "B1-A12") (pinfunction "GND_B1-A12") (pintype "power_in"))
      (node (ref "J2") (pin "2") (pinfunction "MNT_1_2") (pintype "passive"))
      (node (ref "J2") (pin "3") (pinfunction "MNT_2_3") (pintype "passive"))
      (node (ref "J2") (pin "4") (pinfunction "MNT_3_4") (pintype "passive"))
      (node (ref "J2") (pin "5") (pinfunction "MNT_4_5") (pintype "passive"))
      (node (ref "J3") (pin "2") (pinfunction "GND(-)_2") (pintype "passive"))
      (node (ref "J4") (pin "R2") (pinfunction "4_R2") (pintype "passive"))
      (node (ref "J5") (pin "R2") (pinfunction "4_R2") (pintype "passive"))
      (node (ref "P2") (pin "1") (pinfunction "1_1") (pintype "passive"))
      (node (ref "R12") (pin "1") (pinfunction "1_1") (pintype "passive"))
      (node (ref "R14") (pin "1") (pinfunction "1_1") (pintype "passive"))
      (node (ref "R15") (pin "1") (pinfunction "1_1") (pintype "passive"))
      (node (ref "R19") (pin "1") (pinfunction "1_1") (pintype "passive"))
      (node (ref "R20") (pin "1") (pinfunction "1_1") (pintype "passive"))
      (node (ref "R4") (pin "1") (pinfunction "1_1") (pintype "passive"))
      (node (ref "R6") (pin "1") (pinfunction "1_1") (pintype "passive"))
      (node (ref "R9") (pin "1") (pinfunction "1_1") (pintype "passive"))
      (node (ref "SB1") (pin "3") (pinfunction "3_3") (pintype "passive"))
      (node (ref "SW2") (pin "2") (pinfunction "2_2") (pintype "passive"))
      (node (ref "U1") (pin "2") (pinfunction "GND_2") (pintype "power_in"))
      (node (ref "U2") (pin "23") (pinfunction "VSS_1_23") (pintype "power_in"))
      (node (ref "U2") (pin "35") (pinfunction "VSS_2_35") (pintype "power_in"))
      (node (ref "U2") (pin "47") (pinfunction "VSS_3_47") (pintype "power_in"))
      (node (ref "U2") (pin "8") (pinfunction "VSSA_8") (pintype "power_in"))
      (node (ref "U3") (pin "4") (pinfunction "GND_4") (pintype "power_in"))
      (node (ref "U4") (pin "10") (pinfunction "GND_10") (pintype "power_in"))
      (node (ref "U4") (pin "9") (pinfunction "GND_9") (pintype "power_in"))
      (node (ref "U5") (pin "11") (pinfunction "GND_11") (pintype "power_in"))
      (node (ref "U5") (pin "3") (pinfunction "GND_3") (pintype "power_in"))
      (node (ref "U6") (pin "3") (pinfunction "VSS_3") (pintype "power_in"))
      (node (ref "U7") (pin "3") (pinfunction "VSS_3") (pintype "power_in"))
      (node (ref "VR1") (pin "3") (pinfunction "CW_3") (pintype "passive"))
      (node (ref "Y1") (pin "2") (pinfunction "GND_2") (pintype "passive"))
      (node (ref "Y1") (pin "4") (pinfunction "GND_4") (pintype "passive"))
    )
    (net (code "33") (name "Net-(C23-Pad1)") (class "Default")
      (node (ref "C23") (pin "1") (pinfunction "1_1") (pintype "passive"))
      (node (ref "J4") (pin "S") (pinfunction "S_S") (pintype "passive"))
      (node (ref "R18") (pin "2") (pinfunction "2_2") (pintype "passive"))
    )
    (net (code "34") (name "Net-(D1-Pad1)") (class "Default")
      (node (ref "D1") (pin "1") (pinfunction "1_1") (pintype "passive"))
      (node (ref "R8") (pin "1") (pinfunction "1_1") (pintype "passive"))
    )
    (net (code "35") (name "Net-(IC1-PROG)") (class "Default")
      (node (ref "IC1") (pin "5") (pinfunction "PROG_5") (pintype "passive"))
      (node (ref "R7") (pin "2") (pinfunction "2_2") (pintype "passive"))
    )
    (net (code "36") (name "Net-(IC1-~{CHRG})") (class "Default")
      (node (ref "D1") (pin "2") (pinfunction "2_2") (pintype "passive"))
      (node (ref "IC1") (pin "1") (pinfunction "~{CHRG}_1") (pintype "passive"))
    )
    (net (code "37") (name "Net-(J3-OUT(+))") (class "Default")
      (node (ref "C21") (pin "1") (pinfunction "1_1") (pintype "passive"))
      (node (ref "J3") (pin "1") (pinfunction "OUT(+)_1") (pintype "passive"))
      (node (ref "R16") (pin "1") (pinfunction "1_1") (pintype "passive"))
    )
    (net (code "38") (name "Net-(J4-2)") (class "Default")
      (node (ref "J4") (pin "T") (pinfunction "2_T") (pintype "passive"))
      (node (ref "U5") (pin "2") (pinfunction "OUT_L_2") (pintype "output"))
    )
    (net (code "39") (name "Net-(J4-3)") (class "Default")
      (node (ref "J4") (pin "R1") (pinfunction "3_R1") (pintype "passive"))
      (node (ref "U5") (pin "13") (pinfunction "OUT_R_13") (pintype "output"))
    )
    (net (code "40") (name "Net-(U1-EN)") (class "Default")
      (node (ref "R2") (pin "2") (pinfunction "2_2") (pintype "passive"))
      (node (ref "U1") (pin "3") (pinfunction "EN_3") (pintype "passive"))
    )
    (net (code "41") (name "Net-(U3-EN)") (class "Default")
      (node (ref "R1") (pin "2") (pinfunction "2_2") (pintype "passive"))
      (node (ref "U3") (pin "2") (pinfunction "EN_2") (pintype "passive"))
    )
    (net (code "42") (name "Net-(U3-FB)") (class "Default")
      (node (ref "C10") (pin "1") (pinfunction "1_1") (pintype "passive"))
      (node (ref "R3") (pin "1") (pinfunction "1_1") (pintype "passive"))
      (node (ref "R4") (pin "2") (pinfunction "2_2") (pintype "passive"))
      (node (ref "U3") (pin "1") (pinfunction "FB_1") (pintype "passive"))
    )
    (net (code "43") (name "Net-(U3-SW)") (class "Default")
      (node (ref "L1") (pin "2") (pinfunction "2_2") (pintype "passive"))
      (node (ref "U3") (pin "5") (pinfunction "SW_5") (pintype "passive"))
    )
    (net (code "44") (name "Net-(U4-ANT)") (class "Default")
      (node (ref "J2") (pin "1") (pinfunction "1_1") (pintype "passive"))
      (node (ref "U4") (pin "12") (pinfunction "ANT_12") (pintype "bidirectional"))
    )
    (net (code "45") (name "Net-(U5-CN)") (class "Default")
      (node (ref "C25") (pin "2") (pinfunction "2_2") (pintype "passive"))
      (node (ref "U5") (pin "6") (pinfunction "CN_6") (pintype "passive"))
    )
    (net (code "46") (name "Net-(U5-CP)") (class "Default")
      (node (ref "C25") (pin "1") (pinfunction "1_1") (pintype "passive"))
      (node (ref "U5") (pin "9") (pinfunction "CP_9") (pintype "passive"))
    )
    (net (code "47") (name "Net-(U5-GAIN)") (class "Default")
      (node (ref "R20") (pin "2") (pinfunction "2_2") (pintype "passive"))
      (node (ref "U5") (pin "12") (pinfunction "GAIN_12") (pintype "passive"))
    )
    (net (code "48") (name "Net-(U5-VSS)") (class "Default")
      (node (ref "C26") (pin "1") (pinfunction "1_1") (pintype "passive"))
      (node (ref "U5") (pin "5") (pinfunction "VSS_5") (pintype "power_in"))
    )
    (net (code "49") (name "Net-(U6-DIN)") (class "Default")
      (node (ref "U6") (pin "4") (pinfunction "DIN_4") (pintype "input"))
      (node (ref "U7") (pin "2") (pinfunction "DOUT_2") (pintype "output"))
    )
    (net (code "50") (name "Net-(VR1-CCW)") (class "Default")
      (node (ref "R17") (pin "1") (pinfunction "1_1") (pintype "passive"))
      (node (ref "R19") (pin "2") (pinfunction "2_2") (pintype "passive"))
      (node (ref "VR1") (pin "1") (pinfunction "CCW_1") (pintype "passive"))
    )
    (net (code "51") (name "Net-(VR1-WIPER)") (class "Default")
      (node (ref "C24") (pin "2") (pinfunction "2_2") (pintype "passive"))
      (node (ref "VR1") (pin "2") (pinfunction "WIPER_2") (pintype "output"))
    )
    (net (code "52") (name "unconnected-(IC2-IO3-Pad6)") (class "Default")
      (node (ref "IC2") (pin "6") (pinfunction "IO3_6") (pintype "passive"))
    )
    (net (code "53") (name "unconnected-(IC2-VCC-Pad2)") (class "Default")
      (node (ref "IC2") (pin "2") (pinfunction "VCC_2") (pintype "passive"))
    )
    (net (code "54") (name "unconnected-(J1-MNT_1-Pad1)") (class "Default")
      (node (ref "J1") (pin "1") (pinfunction "MNT_1_1") (pintype "power_in+no_connect"))
    )
    (net (code "55") (name "unconnected-(J1-MNT_2-Pad2)") (class "Default")
      (node (ref "J1") (pin "2") (pinfunction "MNT_2_2") (pintype "power_in+no_connect"))
    )
    (net (code "56") (name "unconnected-(J1-MNT_3-Pad3)") (class "Default")
      (node (ref "J1") (pin "3") (pinfunction "MNT_3_3") (pintype "power_in+no_connect"))
    )
    (net (code "57") (name "unconnected-(J1-MNT_4-Pad4)") (class "Default")
      (node (ref "J1") (pin "4") (pinfunction "MNT_4_4") (pintype "power_in+no_connect"))
    )
    (net (code "58") (name "unconnected-(J1-SBU1-PadA8)") (class "Default")
      (node (ref "J1") (pin "A8") (pinfunction "SBU1_A8") (pintype "bidirectional+no_connect"))
    )
    (net (code "59") (name "unconnected-(J1-SBU2-PadB8)") (class "Default")
      (node (ref "J1") (pin "B8") (pinfunction "SBU2_B8") (pintype "power_in+no_connect"))
    )
    (net (code "60") (name "unconnected-(J5-PadS)") (class "Default")
      (node (ref "J5") (pin "S") (pinfunction "S_S") (pintype "passive+no_connect"))
    )
    (net (code "61") (name "unconnected-(SB1-Pad1)") (class "Default")
      (node (ref "SB1") (pin "1") (pinfunction "1_1") (pintype "passive+no_connect"))
    )
    (net (code "62") (name "unconnected-(SW1-1-Pad2)") (class "Default")
      (node (ref "SW1") (pin "2") (pinfunction "1_2") (pintype "passive+no_connect"))
    )
    (net (code "63") (name "unconnected-(SW2-MNT_1-Pad3)") (class "Default")
      (node (ref "SW2") (pin "3") (pinfunction "MNT_1_3") (pintype "passive+no_connect"))
    )
    (net (code "64") (name "unconnected-(SW2-MNT_2-Pad4)") (class "Default")
      (node (ref "SW2") (pin "4") (pinfunction "MNT_2_4") (pintype "passive+no_connect"))
    )
    (net (code "65") (name "unconnected-(U1-N{slash}C-Pad4)") (class "Default")
      (node (ref "U1") (pin "4") (pinfunction "N/C_4") (pintype "passive+no_connect"))
    )
    (net (code "66") (name "unconnected-(U2A-PA0-WKUP-Pad10)") (class "Default")
      (node (ref "U2") (pin "10") (pinfunction "PA0-WKUP_10") (pintype "bidirectional+no_connect"))
    )
    (net (code "67") (name "unconnected-(U2A-PA6-Pad16)") (class "Default")
      (node (ref "U2") (pin "16") (pinfunction "PA6_16") (pintype "bidirectional"))
    )
    (net (code "68") (name "unconnected-(U2A-PA7-Pad17)") (class "Default")
      (node (ref "U2") (pin "17") (pinfunction "PA7_17") (pintype "bidirectional+no_connect"))
    )
    (net (code "69") (name "unconnected-(U2A-PA8-Pad29)") (class "Default")
      (node (ref "U2") (pin "29") (pinfunction "PA8_29") (pintype "bidirectional+no_connect"))
    )
    (net (code "70") (name "unconnected-(U2A-PA9-Pad30)") (class "Default")
      (node (ref "U2") (pin "30") (pinfunction "PA9_30") (pintype "bidirectional+no_connect"))
    )
    (net (code "71") (name "unconnected-(U2A-PA10-Pad31)") (class "Default")
      (node (ref "U2") (pin "31") (pinfunction "PA10_31") (pintype "bidirectional+no_connect"))
    )
    (net (code "72") (name "unconnected-(U2A-PA15-Pad38)") (class "Default")
      (node (ref "U2") (pin "38") (pinfunction "PA15_38") (pintype "bidirectional+no_connect"))
    )
    (net (code "73") (name "unconnected-(U2A-PB0-Pad18)") (class "Default")
      (node (ref "U2") (pin "18") (pinfunction "PB0_18") (pintype "bidirectional"))
    )
    (net (code "74") (name "unconnected-(U2A-PB1-Pad19)") (class "Default")
      (node (ref "U2") (pin "19") (pinfunction "PB1_19") (pintype "bidirectional+no_connect"))
    )
    (net (code "75") (name "unconnected-(U2A-PB2-Pad20)") (class "Default")
      (node (ref "U2") (pin "20") (pinfunction "PB2_20") (pintype "bidirectional+no_connect"))
    )
    (net (code "76") (name "unconnected-(U2A-PB4-Pad40)") (class "Default")
      (node (ref "U2") (pin "40") (pinfunction "PB4_40") (pintype "bidirectional+no_connect"))
    )
    (net (code "77") (name "unconnected-(U2A-PB5-Pad41)") (class "Default")
      (node (ref "U2") (pin "41") (pinfunction "PB5_41") (pintype "bidirectional+no_connect"))
    )
    (net (code "78") (name "unconnected-(U2A-PB6-Pad42)") (class "Default")
      (node (ref "U2") (pin "42") (pinfunction "PB6_42") (pintype "bidirectional+no_connect"))
    )
    (net (code "79") (name "unconnected-(U2A-PB7-Pad43)") (class "Default")
      (node (ref "U2") (pin "43") (pinfunction "PB7_43") (pintype "bidirectional+no_connect"))
    )
    (net (code "80") (name "unconnected-(U2A-PB8-Pad45)") (class "Default")
      (node (ref "U2") (pin "45") (pinfunction "PB8_45") (pintype "bidirectional+no_connect"))
    )
    (net (code "81") (name "unconnected-(U2A-PB9-Pad46)") (class "Default")
      (node (ref "U2") (pin "46") (pinfunction "PB9_46") (pintype "bidirectional+no_connect"))
    )
    (net (code "82") (name "unconnected-(U2A-PB10-Pad21)") (class "Default")
      (node (ref "U2") (pin "21") (pinfunction "PB10_21") (pintype "bidirectional+no_connect"))
    )
    (net (code "83") (name "unconnected-(U2A-PB11-Pad22)") (class "Default")
      (node (ref "U2") (pin "22") (pinfunction "PB11_22") (pintype "bidirectional+no_connect"))
    )
    (net (code "84") (name "unconnected-(U2A-PB12-Pad25)") (class "Default")
      (node (ref "U2") (pin "25") (pinfunction "PB12_25") (pintype "bidirectional"))
    )
    (net (code "85") (name "unconnected-(U2A-PB13-Pad26)") (class "Default")
      (node (ref "U2") (pin "26") (pinfunction "PB13_26") (pintype "bidirectional"))
    )
    (net (code "86") (name "unconnected-(U2A-PB14-Pad27)") (class "Default")
      (node (ref "U2") (pin "27") (pinfunction "PB14_27") (pintype "bidirectional"))
    )
    (net (code "87") (name "unconnected-(U2A-PB15-Pad28)") (class "Default")
      (node (ref "U2") (pin "28") (pinfunction "PB15_28") (pintype "bidirectional+no_connect"))
    )
    (net (code "88") (name "unconnected-(U2A-PC13-TAMPER-RTC-Pad2)") (class "Default")
      (node (ref "U2") (pin "2") (pinfunction "PC13-TAMPER-RTC_2") (pintype "bidirectional+no_connect"))
    )
    (net (code "89") (name "unconnected-(U2A-PC14-OSC32_IN-Pad3)") (class "Default")
      (node (ref "U2") (pin "3") (pinfunction "PC14-OSC32_IN_3") (pintype "bidirectional+no_connect"))
    )
    (net (code "90") (name "unconnected-(U2A-PC15-OSC32_OUT-Pad4)") (class "Default")
      (node (ref "U2") (pin "4") (pinfunction "PC15-OSC32_OUT_4") (pintype "bidirectional+no_connect"))
    )
    (net (code "91") (name "unconnected-(U4-NC-Pad2)") (class "Default")
      (node (ref "U4") (pin "2") (pinfunction "NC_2") (pintype "passive+no_connect"))
    )
    (net (code "92") (name "unconnected-(U4-NC-Pad4)") (class "Default")
      (node (ref "U4") (pin "4") (pinfunction "NC_4") (pintype "passive+no_connect"))
    )
    (net (code "93") (name "unconnected-(U4-NC-Pad11)") (class "Default")
      (node (ref "U4") (pin "11") (pinfunction "NC_11") (pintype "passive+no_connect"))
    )
    (net (code "94") (name "unconnected-(U4-NC-Pad13)") (class "Default")
      (node (ref "U4") (pin "13") (pinfunction "NC_13") (pintype "passive+no_connect"))
    )
    (net (code "95") (name "unconnected-(U4-NC-Pad14)") (class "Default")
      (node (ref "U4") (pin "14") (pinfunction "NC_14") (pintype "passive+no_connect"))
    )
    (net (code "96") (name "unconnected-(U4-NC-Pad15)") (class "Default")
      (node (ref "U4") (pin "15") (pinfunction "NC_15") (pintype "passive+no_connect"))
    )
    (net (code "97") (name "unconnected-(U5-NC-Pad7)") (class "Default")
      (node (ref "U5") (pin "7") (pinfunction "NC_7") (pintype "passive+no_connect"))
    )
    (net (code "98") (name "unconnected-(U5-NC-Pad8)") (class "Default")
      (node (ref "U5") (pin "8") (pinfunction "NC_8") (pintype "passive+no_connect"))
    )
    (net (code "99") (name "unconnected-(U6-DOUT-Pad2)") (class "Default")
      (node (ref "U6") (pin "2") (pinfunction "DOUT_2") (pintype "output+no_connect"))
    )
    (net (code "100") (name "unconnected-(VR1-PadMH1)") (class "Default")
      (node (ref "VR1") (pin "MH1") (pinfunction "MH1_MH1") (pintype "passive+no_connect"))
    )
    (net (code "101") (name "unconnected-(VR1-PadMH2)") (class "Default")
      (node (ref "VR1") (pin "MH2") (pinfunction "MH2_MH2") (pintype "passive+no_connect"))
    )
  )
)
